# alimentazione.net
KiCad netlist of a schematic drawn in EAGLE
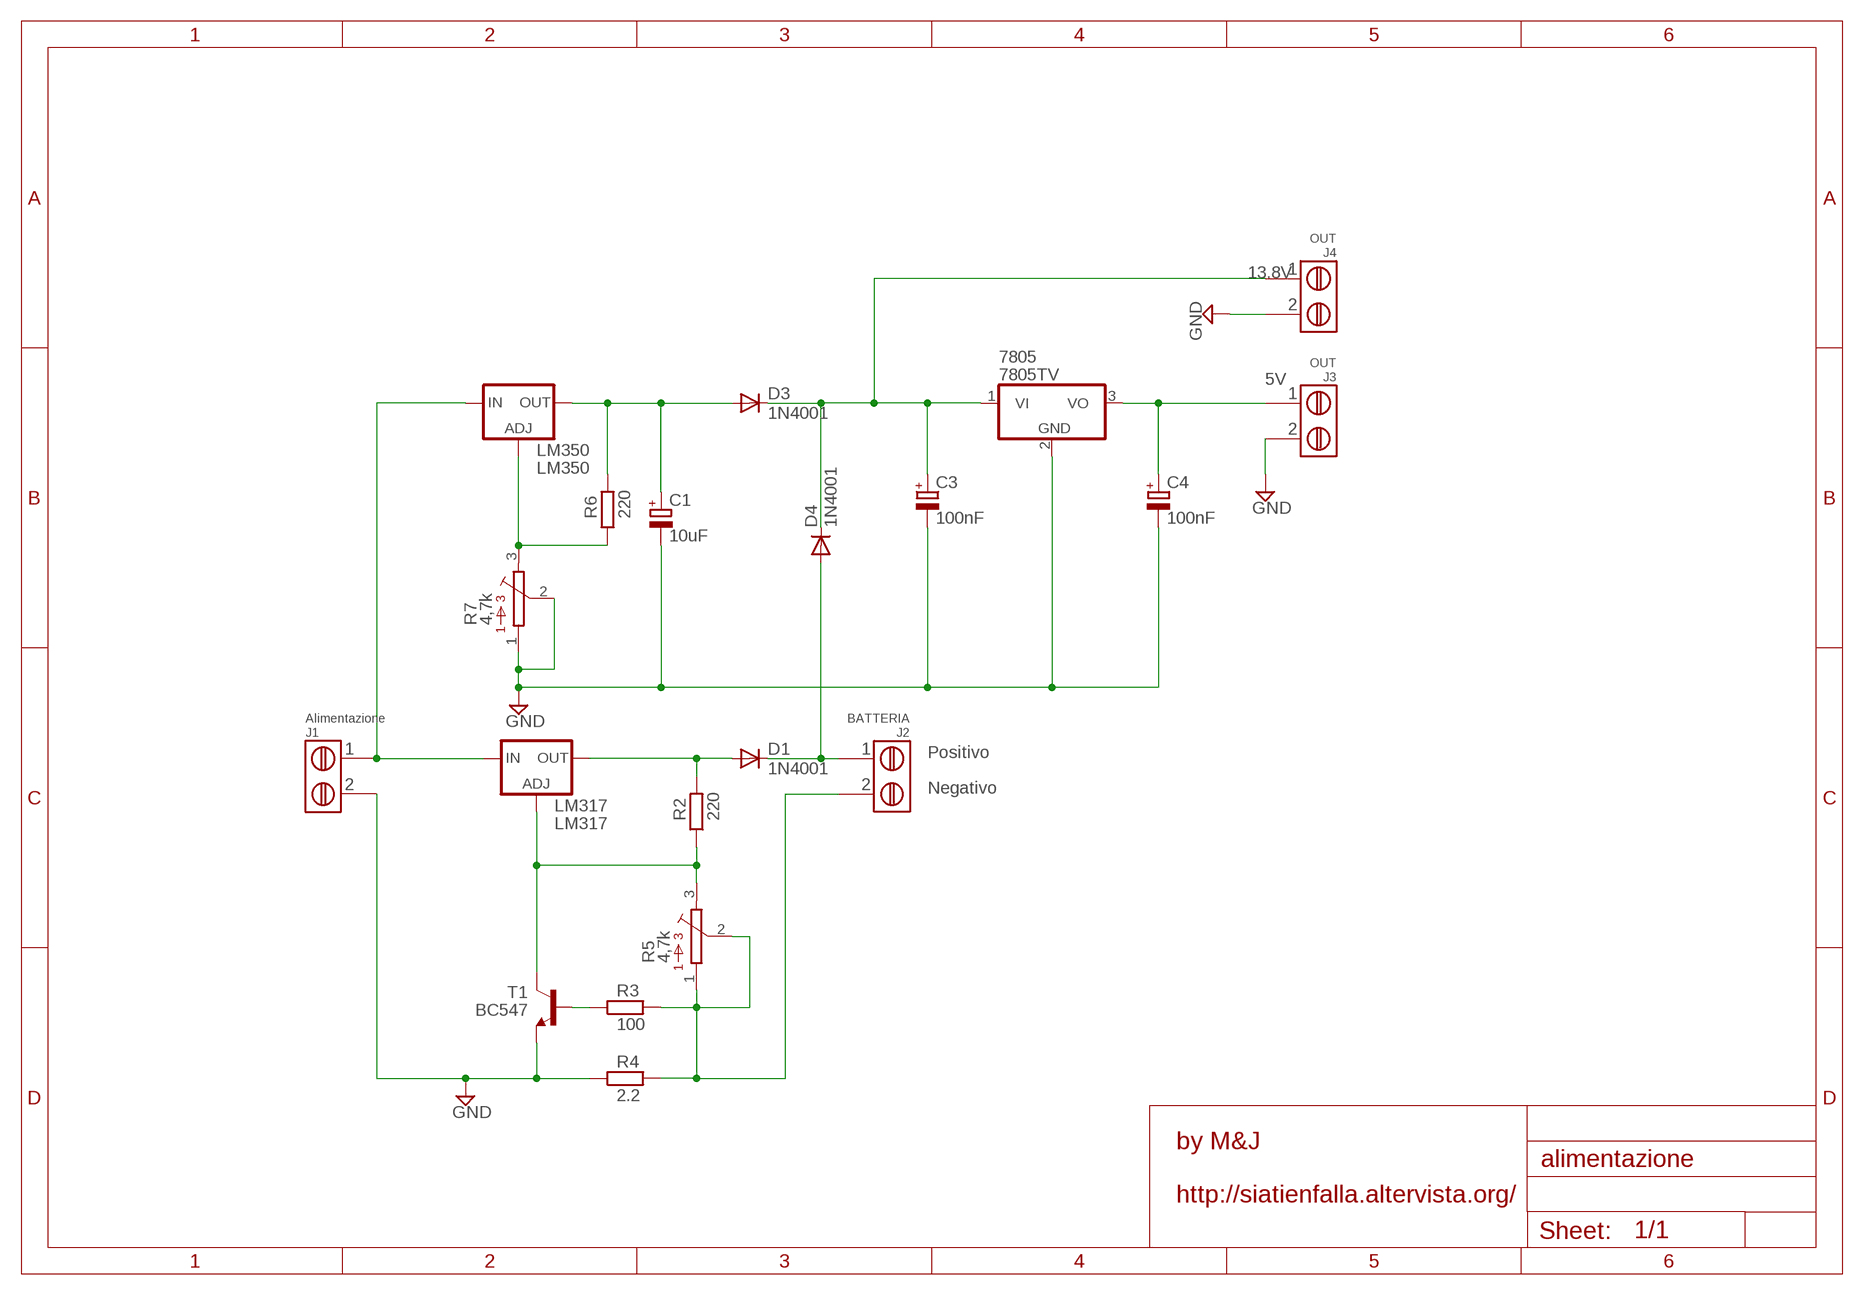
[diagram p0: schematic, sheet 1]

(export (version "E")
  (design (tool "Eeschema 10.0.6"))
  (components
    (comp (ref "7805")
      (value "7805TV")
      (footprint "eagle-import:TO220V")
      (libsource (lib "eagle-import") (part "78TV05"))
    )
    (comp (ref "C1")
      (value "10uF")
      (footprint "eagle-import:E2,5-6")
      (libsource (lib "eagle-import") (part "CPOL-EUE2.5-6"))
    )
    (comp (ref "C3")
      (value "100nF")
      (footprint "eagle-import:E2,5-6")
      (libsource (lib "eagle-import") (part "CPOL-EUE2.5-6"))
    )
    (comp (ref "C4")
      (value "100nF")
      (footprint "eagle-import:E2,5-6")
      (libsource (lib "eagle-import") (part "CPOL-EUE2.5-6"))
    )
    (comp (ref "D1")
      (value "1N4001")
      (footprint "eagle-import:DO41-10")
      (libsource (lib "eagle-import") (part "1N4004"))
    )
    (comp (ref "D3")
      (value "1N4001")
      (footprint "eagle-import:DO41-10")
      (libsource (lib "eagle-import") (part "1N4004"))
    )
    (comp (ref "D4")
      (value "1N4001")
      (footprint "eagle-import:DO41-10")
      (libsource (lib "eagle-import") (part "1N4004"))
    )
    (comp (ref "J1")
      (value "Alimentazione")
      (footprint "eagle-import:MORSETTIERA")
      (libsource (lib "eagle-import") (part "MORSETTIERA"))
    )
    (comp (ref "J2")
      (value "BATTERIA")
      (footprint "eagle-import:MORSETTIERA")
      (libsource (lib "eagle-import") (part "MORSETTIERA"))
    )
    (comp (ref "J3")
      (value "OUT")
      (footprint "eagle-import:MORSETTIERA")
      (libsource (lib "eagle-import") (part "MORSETTIERA"))
    )
    (comp (ref "J4")
      (value "OUT")
      (footprint "eagle-import:MORSETTIERA")
      (libsource (lib "eagle-import") (part "MORSETTIERA"))
    )
    (comp (ref "LM317")
      (value "LM317")
      (footprint "eagle-import:317TS")
      (libsource (lib "eagle-import") (part "LM317TS"))
    )
    (comp (ref "LM350")
      (value "LM350")
      (footprint "eagle-import:317TS")
      (libsource (lib "eagle-import") (part "LM317TS"))
    )
    (comp (ref "R2")
      (value "220")
      (footprint "eagle-import:R1_4W")
      (libsource (lib "eagle-import") (part "RES"))
    )
    (comp (ref "R3")
      (value "100")
      (footprint "eagle-import:R1_4W")
      (libsource (lib "eagle-import") (part "RES"))
    )
    (comp (ref "R4")
      (value "2.2")
      (footprint "eagle-import:R1_4W")
      (libsource (lib "eagle-import") (part "RES"))
    )
    (comp (ref "R5")
      (value "4,7k")
      (footprint "eagle-import:CA9V")
      (libsource (lib "eagle-import") (part "CA9V"))
    )
    (comp (ref "R6")
      (value "220")
      (footprint "eagle-import:R1_4W")
      (libsource (lib "eagle-import") (part "RES"))
    )
    (comp (ref "R7")
      (value "4,7k")
      (footprint "eagle-import:CA9V")
      (libsource (lib "eagle-import") (part "CA9V"))
    )
    (comp (ref "T1")
      (value "BC547")
      (footprint "eagle-import:TO92")
      (libsource (lib "eagle-import") (part "BC547"))
    )
  )
  (nets
    (net (code "1") (name "/5V") (class "Default")
      (node (ref "7805") (pin "3") (pinfunction "VO_3") (pintype "passive"))
      (node (ref "C4") (pin "+") (pinfunction "+_+") (pintype "passive"))
      (node (ref "J3") (pin "1") (pinfunction "1_1") (pintype "passive"))
    )
    (net (code "2") (name "/13.8V") (class "Default")
      (node (ref "7805") (pin "1") (pinfunction "VI_1") (pintype "input"))
      (node (ref "C3") (pin "+") (pinfunction "+_+") (pintype "passive"))
      (node (ref "D3") (pin "C") (pinfunction "K_C") (pintype "passive"))
      (node (ref "D4") (pin "C") (pinfunction "K_C") (pintype "passive"))
      (node (ref "J4") (pin "1") (pinfunction "1_1") (pintype "passive"))
    )
    (net (code "3") (name "GND") (class "Default")
      (node (ref "7805") (pin "2") (pinfunction "GND_2") (pintype "passive"))
      (node (ref "C1") (pin "-") (pinfunction "-_-") (pintype "passive"))
      (node (ref "C3") (pin "-") (pinfunction "-_-") (pintype "passive"))
      (node (ref "C4") (pin "-") (pinfunction "-_-") (pintype "passive"))
      (node (ref "J1") (pin "2") (pinfunction "2_2") (pintype "passive"))
      (node (ref "J3") (pin "2") (pinfunction "2_2") (pintype "passive"))
      (node (ref "J4") (pin "2") (pinfunction "2_2") (pintype "passive"))
      (node (ref "R4") (pin "1") (pinfunction "1_1") (pintype "passive"))
      (node (ref "R7") (pin "1") (pinfunction "1_1") (pintype "passive"))
      (node (ref "R7") (pin "2") (pinfunction "2_2") (pintype "passive"))
      (node (ref "T1") (pin "1") (pinfunction "E_1") (pintype "passive"))
    )
    (net (code "4") (name "Net-(D1-K)") (class "Default")
      (node (ref "D1") (pin "C") (pinfunction "K_C") (pintype "passive"))
      (node (ref "D4") (pin "A") (pinfunction "A_A") (pintype "passive"))
      (node (ref "J2") (pin "1") (pinfunction "1_1") (pintype "passive"))
    )
    (net (code "5") (name "Net-(J2-Pad2)") (class "Default")
      (node (ref "J2") (pin "2") (pinfunction "2_2") (pintype "passive"))
      (node (ref "R3") (pin "2") (pinfunction "2_2") (pintype "passive"))
      (node (ref "R4") (pin "2") (pinfunction "2_2") (pintype "passive"))
      (node (ref "R5") (pin "1") (pinfunction "1_1") (pintype "passive"))
      (node (ref "R5") (pin "2") (pinfunction "2_2") (pintype "passive"))
    )
    (net (code "6") (name "Net-(LM317-ADJ)") (class "Default")
      (node (ref "LM317") (pin "1") (pinfunction "ADJ_1") (pintype "input"))
      (node (ref "R2") (pin "1") (pinfunction "1_1") (pintype "passive"))
      (node (ref "R5") (pin "3") (pinfunction "3_3") (pintype "passive"))
      (node (ref "T1") (pin "3") (pinfunction "C_3") (pintype "passive"))
    )
    (net (code "7") (name "Net-(LM317-IN)") (class "Default")
      (node (ref "J1") (pin "1") (pinfunction "1_1") (pintype "passive"))
      (node (ref "LM317") (pin "3") (pinfunction "IN_3") (pintype "input"))
      (node (ref "LM350") (pin "3") (pinfunction "IN_3") (pintype "input"))
    )
    (net (code "8") (name "Net-(LM317-OUT)") (class "Default")
      (node (ref "D1") (pin "A") (pinfunction "A_A") (pintype "passive"))
      (node (ref "LM317") (pin "2") (pinfunction "OUT_2") (pintype "passive"))
      (node (ref "R2") (pin "2") (pinfunction "2_2") (pintype "passive"))
    )
    (net (code "9") (name "Net-(LM350-ADJ)") (class "Default")
      (node (ref "LM350") (pin "1") (pinfunction "ADJ_1") (pintype "input"))
      (node (ref "R6") (pin "1") (pinfunction "1_1") (pintype "passive"))
      (node (ref "R7") (pin "3") (pinfunction "3_3") (pintype "passive"))
    )
    (net (code "10") (name "Net-(LM350-OUT)") (class "Default")
      (node (ref "C1") (pin "+") (pinfunction "+_+") (pintype "passive"))
      (node (ref "D3") (pin "A") (pinfunction "A_A") (pintype "passive"))
      (node (ref "LM350") (pin "2") (pinfunction "OUT_2") (pintype "passive"))
      (node (ref "R6") (pin "2") (pinfunction "2_2") (pintype "passive"))
    )
    (net (code "11") (name "Net-(T1-B)") (class "Default")
      (node (ref "R3") (pin "1") (pinfunction "1_1") (pintype "passive"))
      (node (ref "T1") (pin "2") (pinfunction "B_2") (pintype "passive"))
    )
  )
)
